# MCU_Power.net
KiCad netlist of a schematic drawn in Altium Designer
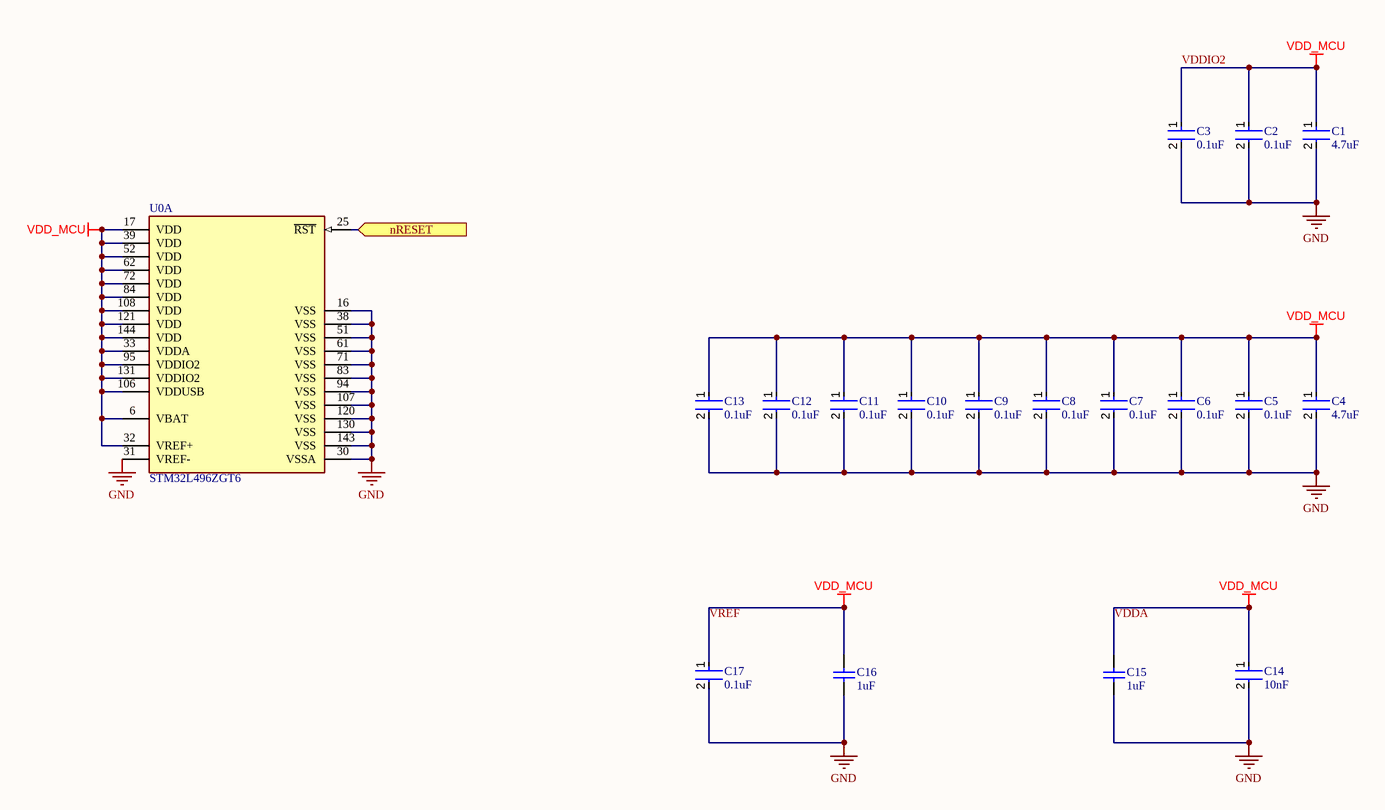
[diagram p0: MCU_Power.SchDoc]

(export (version "E")
  (design (tool "Eeschema 10.0.6"))
  (components
    (comp (ref "C1")
      (value "4.7uF")
      (footprint "FP-GRM188-0_15-IPC_A")
      (description "CAP CER 4.7UF 10V X7S 0603")
      (fields (field (name "TOLERANCE") "10%"))
      (libsource (lib "Altium Content Vault") (part "02cd4be3c70576c341d710602a673aa"))
    )
    (comp (ref "C2")
      (value "0.1uF")
      (footprint "FP-C0603C-CF-MFG")
      (description "CAP CER 0.1UF 50V X7R 0603")
      (fields (field (name "TOLERANCE") "0.1") (field (name "MANUFACTURER") "KEMET"))
      (libsource (lib "Altium Content Vault") (part "b4654b650e69147ec39a6b967a45e02"))
    )
    (comp (ref "C3")
      (value "0.1uF")
      (footprint "FP-C0603C-CF-MFG")
      (description "CAP CER 0.1UF 50V X7R 0603")
      (fields (field (name "TOLERANCE") "0.1") (field (name "MANUFACTURER") "KEMET"))
      (libsource (lib "Altium Content Vault") (part "b4654b650e69147ec39a6b967a45e02"))
    )
    (comp (ref "C4")
      (value "4.7uF")
      (footprint "FP-GRM188-0_15-IPC_A")
      (description "CAP CER 4.7UF 10V X7S 0603")
      (fields (field (name "TOLERANCE") "10%"))
      (libsource (lib "Altium Content Vault") (part "02cd4be3c70576c341d710602a673aa"))
    )
    (comp (ref "C5")
      (value "0.1uF")
      (footprint "FP-C0603C-CF-MFG")
      (description "CAP CER 0.1UF 50V X7R 0603")
      (fields (field (name "TOLERANCE") "0.1") (field (name "MANUFACTURER") "KEMET"))
      (libsource (lib "Altium Content Vault") (part "b4654b650e69147ec39a6b967a45e02"))
    )
    (comp (ref "C6")
      (value "0.1uF")
      (footprint "FP-C0603C-CF-MFG")
      (description "CAP CER 0.1UF 50V X7R 0603")
      (fields (field (name "TOLERANCE") "0.1") (field (name "MANUFACTURER") "KEMET"))
      (libsource (lib "Altium Content Vault") (part "b4654b650e69147ec39a6b967a45e02"))
    )
    (comp (ref "C7")
      (value "0.1uF")
      (footprint "FP-C0603C-CF-MFG")
      (description "CAP CER 0.1UF 50V X7R 0603")
      (fields (field (name "TOLERANCE") "0.1") (field (name "MANUFACTURER") "KEMET"))
      (libsource (lib "Altium Content Vault") (part "b4654b650e69147ec39a6b967a45e02"))
    )
    (comp (ref "C8")
      (value "0.1uF")
      (footprint "FP-C0603C-CF-MFG")
      (description "CAP CER 0.1UF 50V X7R 0603")
      (fields (field (name "TOLERANCE") "0.1") (field (name "MANUFACTURER") "KEMET"))
      (libsource (lib "Altium Content Vault") (part "b4654b650e69147ec39a6b967a45e02"))
    )
    (comp (ref "C9")
      (value "0.1uF")
      (footprint "FP-C0603C-CF-MFG")
      (description "CAP CER 0.1UF 50V X7R 0603")
      (fields (field (name "TOLERANCE") "0.1") (field (name "MANUFACTURER") "KEMET"))
      (libsource (lib "Altium Content Vault") (part "b4654b650e69147ec39a6b967a45e02"))
    )
    (comp (ref "C10")
      (value "0.1uF")
      (footprint "FP-C0603C-CF-MFG")
      (description "CAP CER 0.1UF 50V X7R 0603")
      (fields (field (name "TOLERANCE") "0.1") (field (name "MANUFACTURER") "KEMET"))
      (libsource (lib "Altium Content Vault") (part "b4654b650e69147ec39a6b967a45e02"))
    )
    (comp (ref "C11")
      (value "0.1uF")
      (footprint "FP-C0603C-CF-MFG")
      (description "CAP CER 0.1UF 50V X7R 0603")
      (fields (field (name "TOLERANCE") "0.1") (field (name "MANUFACTURER") "KEMET"))
      (libsource (lib "Altium Content Vault") (part "b4654b650e69147ec39a6b967a45e02"))
    )
    (comp (ref "C12")
      (value "0.1uF")
      (footprint "FP-C0603C-CF-MFG")
      (description "CAP CER 0.1UF 50V X7R 0603")
      (fields (field (name "TOLERANCE") "0.1") (field (name "MANUFACTURER") "KEMET"))
      (libsource (lib "Altium Content Vault") (part "b4654b650e69147ec39a6b967a45e02"))
    )
    (comp (ref "C13")
      (value "0.1uF")
      (footprint "FP-C0603C-CF-MFG")
      (description "CAP CER 0.1UF 50V X7R 0603")
      (fields (field (name "TOLERANCE") "0.1") (field (name "MANUFACTURER") "KEMET"))
      (libsource (lib "Altium Content Vault") (part "b4654b650e69147ec39a6b967a45e02"))
    )
    (comp (ref "C14")
      (value "10nF")
      (footprint "FP-GRM188-0_1-e0_2_0_5-IPC_A")
      (description "Chip Multilayer Ceramic Capacitors for General Purpose, 0603, 10000pF, X7R, 15%, 10%, 100V")
      (fields (field (name "VOLTAGE") "100V") (field (name "TOLERANCE") "10%"))
      (libsource (lib "Altium Content Vault") (part "11868f565c42a9108669ba33697ecf6"))
    )
    (comp (ref "C15")
      (value "1uF")
      (footprint "CAPC1608X90X35LL15T15")
      (fields (field (name "MANUFACTURER") "Kemet") (field (name "PART NUMBER") "C0603C105K4RACTU"))
      (libsource (lib "Altium Content Vault") (part "CAP"))
    )
    (comp (ref "C16")
      (value "1uF")
      (footprint "CAPC1608X90X35LL15T15")
      (fields (field (name "MANUFACTURER") "Kemet") (field (name "PART NUMBER") "C0603C105K4RACTU"))
      (libsource (lib "Altium Content Vault") (part "CAP"))
    )
    (comp (ref "C17")
      (value "0.1uF")
      (footprint "FP-C0603C-CF-MFG")
      (description "CAP CER 0.1UF 50V X7R 0603")
      (fields (field (name "TOLERANCE") "0.1") (field (name "MANUFACTURER") "KEMET"))
      (libsource (lib "Altium Content Vault") (part "b4654b650e69147ec39a6b967a45e02"))
    )
    (comp (ref "U0")
      (value "STM32L496ZGT6")
      (footprint "FP-LQFP144-1A-MFG")
      (description "IC MCU 32BIT 1MB FLASH 144LQFP")
      (libsource (lib "Altium Content Vault") (part "f8f598a4e7bf6abd6ff1d35fb83b48f"))
    )
  )
  (nets
    (net (code "1") (name "/nRESET") (class "Default")
      (node (ref "U0") (pin "25") (pinfunction "~{RST}_25") (pintype "input"))
    )
    (net (code "2") (name "GND") (class "Default")
      (node (ref "C1") (pin "2") (pinfunction "2_2") (pintype "passive"))
      (node (ref "C10") (pin "2") (pinfunction "2_2") (pintype "passive"))
      (node (ref "C11") (pin "2") (pinfunction "2_2") (pintype "passive"))
      (node (ref "C12") (pin "2") (pinfunction "2_2") (pintype "passive"))
      (node (ref "C13") (pin "2") (pinfunction "2_2") (pintype "passive"))
      (node (ref "C14") (pin "2") (pinfunction "2_2") (pintype "passive"))
      (node (ref "C15") (pin "2") (pinfunction "2_2") (pintype "passive"))
      (node (ref "C16") (pin "2") (pinfunction "2_2") (pintype "passive"))
      (node (ref "C17") (pin "2") (pinfunction "2_2") (pintype "passive"))
      (node (ref "C2") (pin "2") (pinfunction "2_2") (pintype "passive"))
      (node (ref "C3") (pin "2") (pinfunction "2_2") (pintype "passive"))
      (node (ref "C4") (pin "2") (pinfunction "2_2") (pintype "passive"))
      (node (ref "C5") (pin "2") (pinfunction "2_2") (pintype "passive"))
      (node (ref "C6") (pin "2") (pinfunction "2_2") (pintype "passive"))
      (node (ref "C7") (pin "2") (pinfunction "2_2") (pintype "passive"))
      (node (ref "C8") (pin "2") (pinfunction "2_2") (pintype "passive"))
      (node (ref "C9") (pin "2") (pinfunction "2_2") (pintype "passive"))
      (node (ref "U0") (pin "107") (pinfunction "VSS_107") (pintype "power_in"))
      (node (ref "U0") (pin "120") (pinfunction "VSS_120") (pintype "power_in"))
      (node (ref "U0") (pin "130") (pinfunction "VSS_130") (pintype "power_in"))
      (node (ref "U0") (pin "143") (pinfunction "VSS_143") (pintype "power_in"))
      (node (ref "U0") (pin "16") (pinfunction "VSS_16") (pintype "power_in"))
      (node (ref "U0") (pin "30") (pinfunction "VSSA_30") (pintype "power_in"))
      (node (ref "U0") (pin "31") (pinfunction "VREF-_31") (pintype "power_in"))
      (node (ref "U0") (pin "38") (pinfunction "VSS_38") (pintype "power_in"))
      (node (ref "U0") (pin "51") (pinfunction "VSS_51") (pintype "power_in"))
      (node (ref "U0") (pin "61") (pinfunction "VSS_61") (pintype "power_in"))
      (node (ref "U0") (pin "71") (pinfunction "VSS_71") (pintype "power_in"))
      (node (ref "U0") (pin "83") (pinfunction "VSS_83") (pintype "power_in"))
      (node (ref "U0") (pin "94") (pinfunction "VSS_94") (pintype "power_in"))
    )
    (net (code "3") (name "VDD_MCU") (class "Default")
      (node (ref "C1") (pin "1") (pinfunction "1_1") (pintype "passive"))
      (node (ref "C10") (pin "1") (pinfunction "1_1") (pintype "passive"))
      (node (ref "C11") (pin "1") (pinfunction "1_1") (pintype "passive"))
      (node (ref "C12") (pin "1") (pinfunction "1_1") (pintype "passive"))
      (node (ref "C13") (pin "1") (pinfunction "1_1") (pintype "passive"))
      (node (ref "C14") (pin "1") (pinfunction "1_1") (pintype "passive"))
      (node (ref "C15") (pin "1") (pinfunction "1_1") (pintype "passive"))
      (node (ref "C16") (pin "1") (pinfunction "1_1") (pintype "passive"))
      (node (ref "C17") (pin "1") (pinfunction "1_1") (pintype "passive"))
      (node (ref "C2") (pin "1") (pinfunction "1_1") (pintype "passive"))
      (node (ref "C3") (pin "1") (pinfunction "1_1") (pintype "passive"))
      (node (ref "C4") (pin "1") (pinfunction "1_1") (pintype "passive"))
      (node (ref "C5") (pin "1") (pinfunction "1_1") (pintype "passive"))
      (node (ref "C6") (pin "1") (pinfunction "1_1") (pintype "passive"))
      (node (ref "C7") (pin "1") (pinfunction "1_1") (pintype "passive"))
      (node (ref "C8") (pin "1") (pinfunction "1_1") (pintype "passive"))
      (node (ref "C9") (pin "1") (pinfunction "1_1") (pintype "passive"))
      (node (ref "U0") (pin "106") (pinfunction "VDDUSB_106") (pintype "power_in"))
      (node (ref "U0") (pin "108") (pinfunction "VDD_108") (pintype "power_in"))
      (node (ref "U0") (pin "121") (pinfunction "VDD_121") (pintype "power_in"))
      (node (ref "U0") (pin "131") (pinfunction "VDDIO2_131") (pintype "power_in"))
      (node (ref "U0") (pin "144") (pinfunction "VDD_144") (pintype "power_in"))
      (node (ref "U0") (pin "17") (pinfunction "VDD_17") (pintype "power_in"))
      (node (ref "U0") (pin "32") (pinfunction "VREF+_32") (pintype "power_in"))
      (node (ref "U0") (pin "33") (pinfunction "VDDA_33") (pintype "power_in"))
      (node (ref "U0") (pin "39") (pinfunction "VDD_39") (pintype "power_in"))
      (node (ref "U0") (pin "52") (pinfunction "VDD_52") (pintype "power_in"))
      (node (ref "U0") (pin "6") (pinfunction "VBAT_6") (pintype "power_in"))
      (node (ref "U0") (pin "62") (pinfunction "VDD_62") (pintype "power_in"))
      (node (ref "U0") (pin "72") (pinfunction "VDD_72") (pintype "power_in"))
      (node (ref "U0") (pin "84") (pinfunction "VDD_84") (pintype "power_in"))
      (node (ref "U0") (pin "95") (pinfunction "VDDIO2_95") (pintype "power_in"))
    )
  )
)
